# Vario_0_1_Ultra_Mini.net
KiCad netlist of a schematic drawn in EAGLE
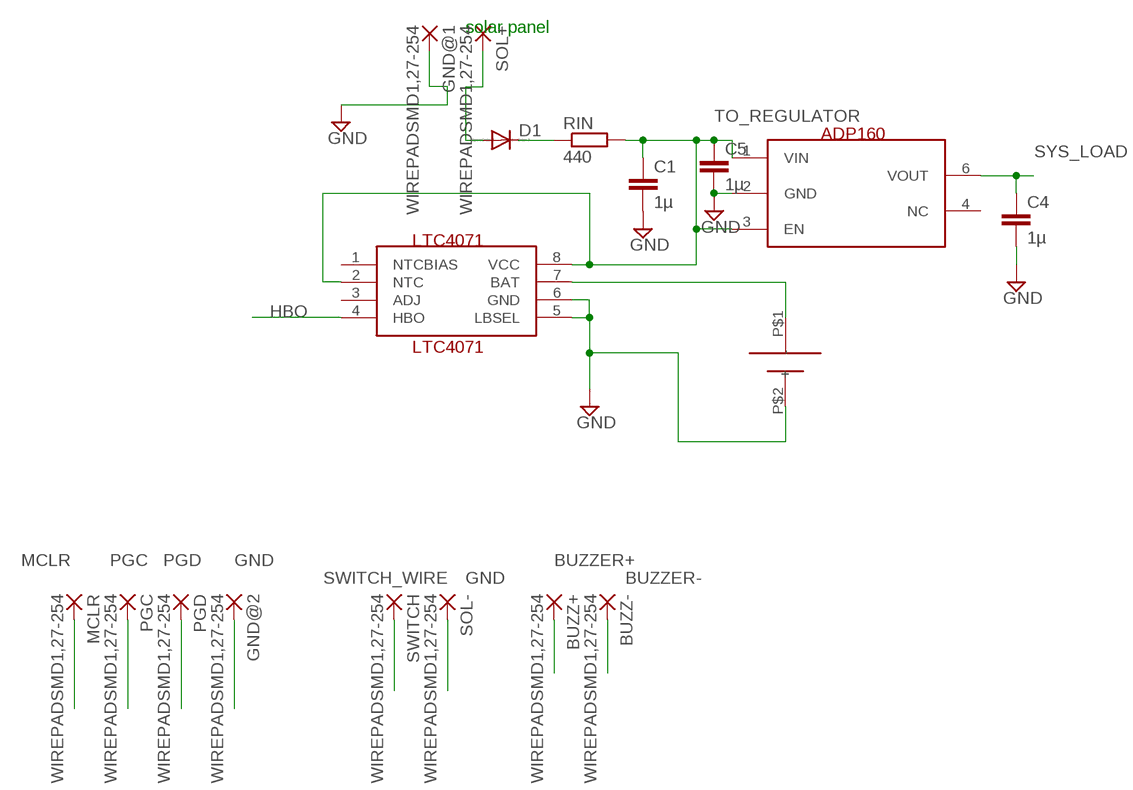
[diagram p0: schematic, sheet 1]
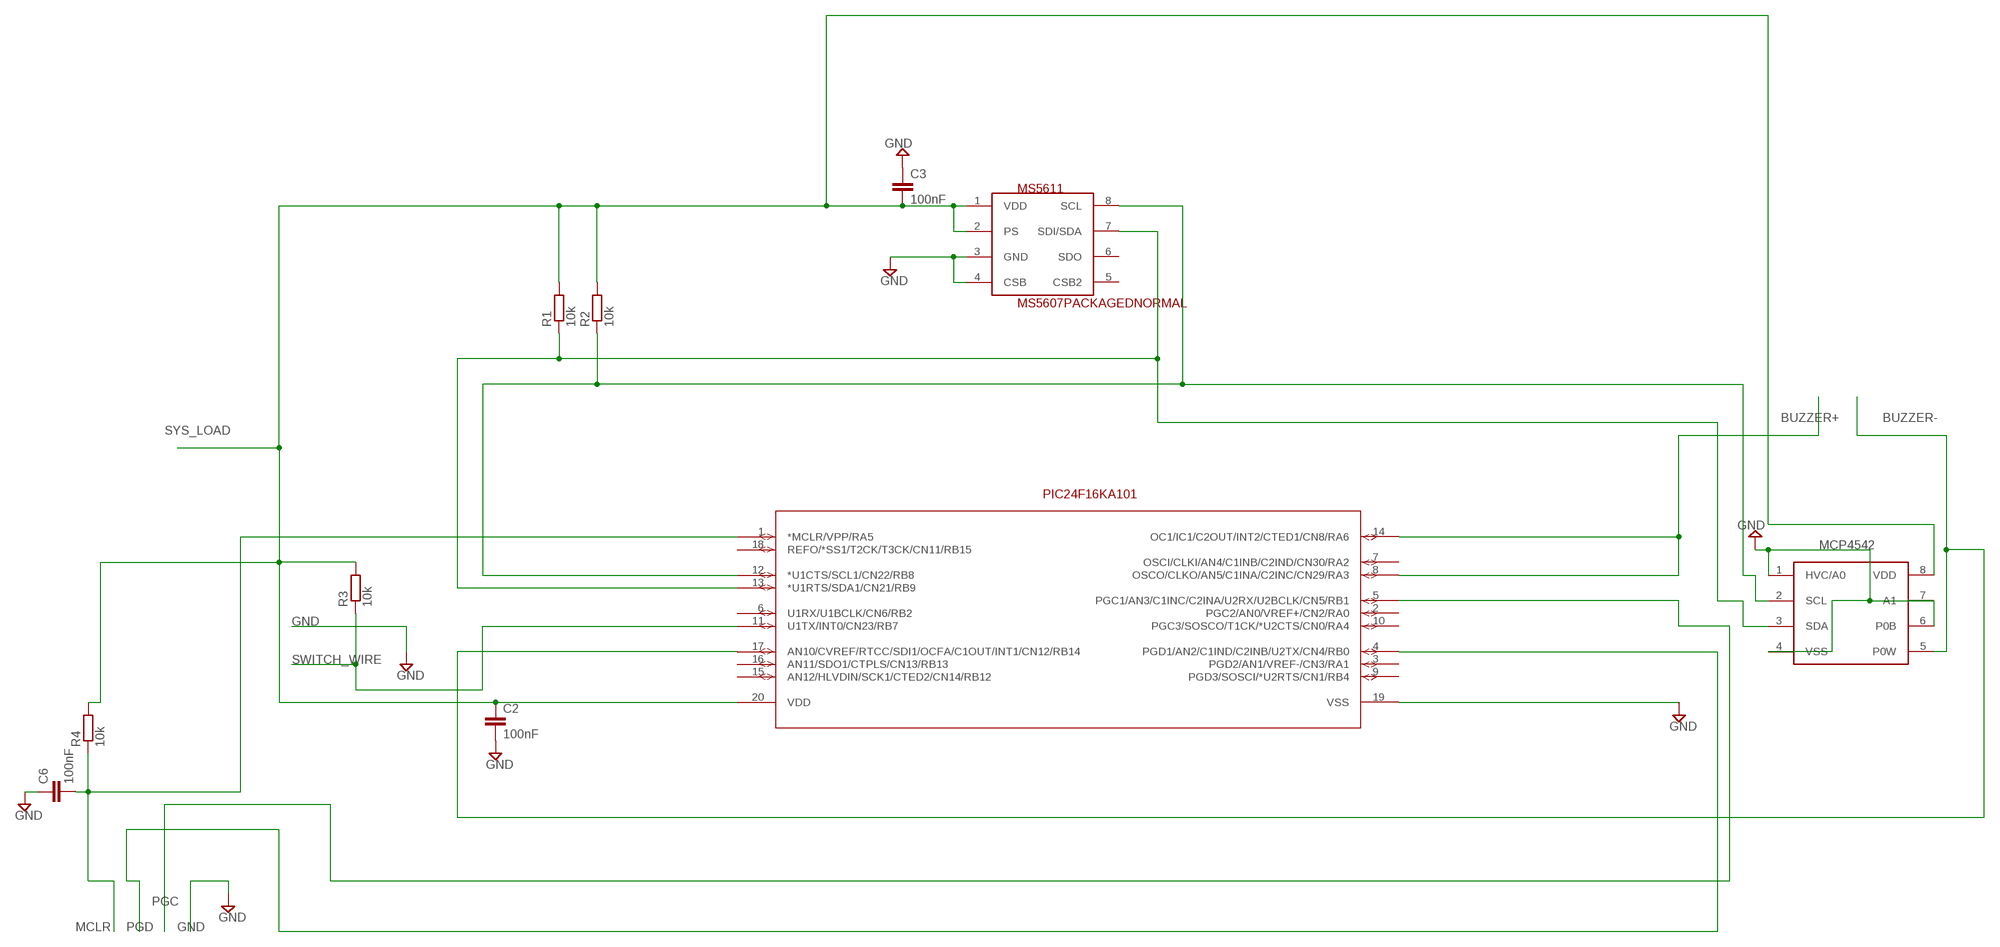
[diagram p1: schematic, sheet 2]

(export (version "E")
  (design (tool "Eeschema 10.0.6"))
  (components
    (comp (ref "ADP160")
      (value "ADP160/161/162/163")
      (footprint "eagle-import:TSOT23-6_DDC")
      (libsource (lib "eagle-import") (part "ADP160/161/162/163"))
    )
    (comp (ref "BATT+")
      (value "VARIO_LIPO")
      (footprint "eagle-import:VARIO_LIPO")
      (libsource (lib "eagle-import") (part "VARIO_LIPO"))
    )
    (comp (ref "BUZZ+")
      (value "WIREPADSMD1,27-254")
      (footprint "eagle-import:SMD1,27-2,54")
      (libsource (lib "eagle-import") (part "WIREPADSMD1,27-254"))
    )
    (comp (ref "BUZZ-")
      (value "WIREPADSMD1,27-254")
      (footprint "eagle-import:SMD1,27-2,54")
      (libsource (lib "eagle-import") (part "WIREPADSMD1,27-254"))
    )
    (comp (ref "C1")
      (value "1µ")
      (footprint "eagle-import:C0603")
      (libsource (lib "eagle-import") (part "C-EUC0603"))
    )
    (comp (ref "C4")
      (value "1µ")
      (footprint "eagle-import:C0603")
      (libsource (lib "eagle-import") (part "C-EUC0603"))
    )
    (comp (ref "C5")
      (value "1µ")
      (footprint "eagle-import:C0603")
      (libsource (lib "eagle-import") (part "C-EUC0603"))
    )
    (comp (ref "D1")
      (value "DIODE-SOD323-R")
      (footprint "eagle-import:SOD323-R")
      (libsource (lib "eagle-import") (part "DIODE-SOD323-R"))
    )
    (comp (ref "GND@1")
      (value "WIREPADSMD1,27-254")
      (footprint "eagle-import:SMD1,27-2,54")
      (libsource (lib "eagle-import") (part "WIREPADSMD1,27-254"))
    )
    (comp (ref "GND@2")
      (value "WIREPADSMD1,27-254")
      (footprint "eagle-import:SMD1,27-2,54")
      (libsource (lib "eagle-import") (part "WIREPADSMD1,27-254"))
    )
    (comp (ref "LTC4071")
      (value "LTC4071")
      (footprint "eagle-import:MSOP8")
      (libsource (lib "eagle-import") (part "LTC4071"))
    )
    (comp (ref "MCLR")
      (value "WIREPADSMD1,27-254")
      (footprint "eagle-import:SMD1,27-2,54")
      (libsource (lib "eagle-import") (part "WIREPADSMD1,27-254"))
    )
    (comp (ref "PGC")
      (value "WIREPADSMD1,27-254")
      (footprint "eagle-import:SMD1,27-2,54")
      (libsource (lib "eagle-import") (part "WIREPADSMD1,27-254"))
    )
    (comp (ref "PGD")
      (value "WIREPADSMD1,27-254")
      (footprint "eagle-import:SMD1,27-2,54")
      (libsource (lib "eagle-import") (part "WIREPADSMD1,27-254"))
    )
    (comp (ref "RIN")
      (value "440")
      (footprint "eagle-import:R0603")
      (libsource (lib "eagle-import") (part "R-EU_R0603"))
    )
    (comp (ref "SOL+")
      (value "WIREPADSMD1,27-254")
      (footprint "eagle-import:SMD1,27-2,54")
      (libsource (lib "eagle-import") (part "WIREPADSMD1,27-254"))
    )
    (comp (ref "SOL-")
      (value "WIREPADSMD1,27-254")
      (footprint "eagle-import:SMD1,27-2,54")
      (libsource (lib "eagle-import") (part "WIREPADSMD1,27-254"))
    )
    (comp (ref "SWITCH")
      (value "WIREPADSMD1,27-254")
      (footprint "eagle-import:SMD1,27-2,54")
      (libsource (lib "eagle-import") (part "WIREPADSMD1,27-254"))
    )
    (comp (ref "C2")
      (value "100nF")
      (footprint "eagle-import:C0603")
      (libsource (lib "eagle-import") (part "C-EUC0603"))
    )
    (comp (ref "C3")
      (value "100nF")
      (footprint "eagle-import:C0603")
      (libsource (lib "eagle-import") (part "C-EUC0603"))
    )
    (comp (ref "C6")
      (value "100nF")
      (footprint "eagle-import:C0603")
      (libsource (lib "eagle-import") (part "C-EUC0603"))
    )
    (comp (ref "MCP4542")
      (value "MCP4542")
      (footprint "eagle-import:MSOP8")
      (libsource (lib "eagle-import") (part "MCP4542"))
    )
    (comp (ref "MS5611")
      (value "MS5607PACKAGEDNORMAL")
      (footprint "eagle-import:MS5607-02BA03")
      (libsource (lib "eagle-import") (part "MS5607PACKAGEDNORMAL"))
    )
    (comp (ref "PIC24F16KA101")
      (value "PIC24F16KA101-X_")
      (footprint "eagle-import:SSOP20_MC")
      (libsource (lib "eagle-import") (part "PIC24F16KA101-X_"))
    )
    (comp (ref "R1")
      (value "10k")
      (footprint "eagle-import:R0603")
      (libsource (lib "eagle-import") (part "R-EU_R0603"))
    )
    (comp (ref "R2")
      (value "10k")
      (footprint "eagle-import:R0603")
      (libsource (lib "eagle-import") (part "R-EU_R0603"))
    )
    (comp (ref "R3")
      (value "10k")
      (footprint "eagle-import:R0603")
      (libsource (lib "eagle-import") (part "R-EU_R0603"))
    )
    (comp (ref "R4")
      (value "10k")
      (footprint "eagle-import:R0603")
      (libsource (lib "eagle-import") (part "R-EU_R0603"))
    )
  )
  (nets
    (net (code "1") (name "BUZZER+") (class "Default")
      (node (ref "BUZZ+") (pin "1") (pinfunction "P_1") (pintype "passive"))
      (node (ref "PIC24F16KA101") (pin "14") (pinfunction "OC1/IC1/C2OUT/INT2/CTED1/CN8/RA6_14") (pintype "passive"))
      (node (ref "PIC24F16KA101") (pin "8") (pinfunction "OSCO/CLKO/AN5/C1INA/C2INC/CN29/RA3_8") (pintype "passive"))
    )
    (net (code "2") (name "BUZZER-") (class "Default")
      (node (ref "BUZZ-") (pin "1") (pinfunction "P_1") (pintype "passive"))
      (node (ref "MCP4542") (pin "5") (pinfunction "P0W_5") (pintype "bidirectional"))
      (node (ref "PIC24F16KA101") (pin "17") (pinfunction "AN10/CVREF/RTCC/SDI1/OCFA/C1OUT/INT1/CN12/RB14_17") (pintype "passive"))
    )
    (net (code "3") (name "GND") (class "Default")
      (node (ref "ADP160") (pin "2") (pinfunction "GND_2") (pintype "power_in"))
      (node (ref "BATT+") (pin "P$2") (pinfunction "-_P$2") (pintype "bidirectional"))
      (node (ref "C1") (pin "2") (pinfunction "2_2") (pintype "passive"))
      (node (ref "C2") (pin "2") (pinfunction "2_2") (pintype "passive"))
      (node (ref "C3") (pin "1") (pinfunction "1_1") (pintype "passive"))
      (node (ref "C4") (pin "2") (pinfunction "2_2") (pintype "passive"))
      (node (ref "C5") (pin "2") (pinfunction "2_2") (pintype "passive"))
      (node (ref "C6") (pin "1") (pinfunction "1_1") (pintype "passive"))
      (node (ref "GND@1") (pin "1") (pinfunction "P_1") (pintype "passive"))
      (node (ref "GND@2") (pin "1") (pinfunction "P_1") (pintype "passive"))
      (node (ref "LTC4071") (pin "5") (pinfunction "LBSEL_5") (pintype "output"))
      (node (ref "LTC4071") (pin "6") (pinfunction "GND_6") (pintype "input"))
      (node (ref "MCP4542") (pin "1") (pinfunction "HVC/A0_1") (pintype "input"))
      (node (ref "MCP4542") (pin "4") (pinfunction "VSS_4") (pintype "bidirectional"))
      (node (ref "MCP4542") (pin "6") (pinfunction "P0B_6") (pintype "bidirectional"))
      (node (ref "MCP4542") (pin "7") (pinfunction "A1_7") (pintype "bidirectional"))
      (node (ref "MS5611") (pin "3") (pinfunction "GND_3") (pintype "power_in"))
      (node (ref "MS5611") (pin "4") (pinfunction "CSB_4") (pintype "input"))
      (node (ref "PIC24F16KA101") (pin "19") (pinfunction "VSS_19") (pintype "passive"))
      (node (ref "SOL-") (pin "1") (pinfunction "P_1") (pintype "passive"))
    )
    (net (code "4") (name "HBO") (class "Default")
      (node (ref "LTC4071") (pin "4") (pinfunction "HBO_4") (pintype "output"))
    )
    (net (code "5") (name "MCLR") (class "Default")
      (node (ref "C6") (pin "2") (pinfunction "2_2") (pintype "passive"))
      (node (ref "MCLR") (pin "1") (pinfunction "P_1") (pintype "passive"))
      (node (ref "PIC24F16KA101") (pin "1") (pinfunction "*MCLR/VPP/RA5_1") (pintype "passive"))
      (node (ref "R4") (pin "1") (pinfunction "1_1") (pintype "passive"))
    )
    (net (code "6") (name "Net-(BATT+-+)") (class "Default")
      (node (ref "BATT+") (pin "P$1") (pinfunction "+_P$1") (pintype "bidirectional"))
      (node (ref "LTC4071") (pin "7") (pinfunction "BAT_7") (pintype "bidirectional"))
    )
    (net (code "7") (name "Net-(D1-PadC)") (class "Default")
      (node (ref "D1") (pin "C") (pinfunction "C_C") (pintype "passive"))
      (node (ref "RIN") (pin "1") (pinfunction "1_1") (pintype "passive"))
    )
    (net (code "8") (name "Net-(MCP4542-SCL)") (class "Default")
      (node (ref "MCP4542") (pin "2") (pinfunction "SCL_2") (pintype "bidirectional"))
      (node (ref "MS5611") (pin "8") (pinfunction "SCL_8") (pintype "input"))
      (node (ref "PIC24F16KA101") (pin "12") (pinfunction "*U1CTS/SCL1/CN22/RB8_12") (pintype "passive"))
      (node (ref "R2") (pin "1") (pinfunction "1_1") (pintype "passive"))
    )
    (net (code "9") (name "Net-(MCP4542-SDA)") (class "Default")
      (node (ref "MCP4542") (pin "3") (pinfunction "SDA_3") (pintype "bidirectional"))
      (node (ref "MS5611") (pin "7") (pinfunction "SDI/SDA_7") (pintype "bidirectional"))
      (node (ref "PIC24F16KA101") (pin "13") (pinfunction "*U1RTS/SDA1/CN21/RB9_13") (pintype "passive"))
      (node (ref "R1") (pin "1") (pinfunction "1_1") (pintype "passive"))
    )
    (net (code "10") (name "Net-(SOL+-P)") (class "Default")
      (node (ref "D1") (pin "A") (pinfunction "A_A") (pintype "passive"))
      (node (ref "SOL+") (pin "1") (pinfunction "P_1") (pintype "passive"))
    )
    (net (code "11") (name "PGC") (class "Default")
      (node (ref "PGC") (pin "1") (pinfunction "P_1") (pintype "passive"))
      (node (ref "PIC24F16KA101") (pin "5") (pinfunction "PGC1/AN3/C1INC/C2INA/U2RX/U2BCLK/CN5/RB1_5") (pintype "passive"))
    )
    (net (code "12") (name "PGD") (class "Default")
      (node (ref "PGD") (pin "1") (pinfunction "P_1") (pintype "passive"))
      (node (ref "PIC24F16KA101") (pin "4") (pinfunction "PGD1/AN2/C1IND/C2INB/U2TX/CN4/RB0_4") (pintype "passive"))
    )
    (net (code "13") (name "SWITCH_WIRE") (class "Default")
      (node (ref "PIC24F16KA101") (pin "11") (pinfunction "U1TX/INT0/CN23/RB7_11") (pintype "passive"))
      (node (ref "R3") (pin "1") (pinfunction "1_1") (pintype "passive"))
      (node (ref "SWITCH") (pin "1") (pinfunction "P_1") (pintype "passive"))
    )
    (net (code "14") (name "SYS_LOAD") (class "Default")
      (node (ref "ADP160") (pin "6") (pinfunction "VOUT_6") (pintype "bidirectional"))
      (node (ref "C2") (pin "1") (pinfunction "1_1") (pintype "passive"))
      (node (ref "C3") (pin "2") (pinfunction "2_2") (pintype "passive"))
      (node (ref "C4") (pin "1") (pinfunction "1_1") (pintype "passive"))
      (node (ref "MCP4542") (pin "8") (pinfunction "VDD_8") (pintype "bidirectional"))
      (node (ref "MS5611") (pin "1") (pinfunction "VDD_1") (pintype "power_in"))
      (node (ref "MS5611") (pin "2") (pinfunction "PS_2") (pintype "input"))
      (node (ref "PIC24F16KA101") (pin "20") (pinfunction "VDD_20") (pintype "passive"))
      (node (ref "R1") (pin "2") (pinfunction "2_2") (pintype "passive"))
      (node (ref "R2") (pin "2") (pinfunction "2_2") (pintype "passive"))
      (node (ref "R3") (pin "2") (pinfunction "2_2") (pintype "passive"))
      (node (ref "R4") (pin "2") (pinfunction "2_2") (pintype "passive"))
    )
    (net (code "15") (name "TO_REGULATOR") (class "Default")
      (node (ref "ADP160") (pin "1") (pinfunction "VIN_1") (pintype "tri_state"))
      (node (ref "ADP160") (pin "3") (pinfunction "EN_3") (pintype "input"))
      (node (ref "C1") (pin "1") (pinfunction "1_1") (pintype "passive"))
      (node (ref "C5") (pin "1") (pinfunction "1_1") (pintype "passive"))
      (node (ref "LTC4071") (pin "2") (pinfunction "NTC_2") (pintype "input"))
      (node (ref "LTC4071") (pin "8") (pinfunction "VCC_8") (pintype "input"))
      (node (ref "RIN") (pin "2") (pinfunction "2_2") (pintype "passive"))
    )
    (net (code "16") (name "unconnected-(ADP160-NC-Pad4)") (class "Default")
      (node (ref "ADP160") (pin "4") (pinfunction "NC_4") (pintype "no_connect"))
    )
    (net (code "17") (name "unconnected-(LTC4071-ADJ-Pad3)") (class "Default")
      (node (ref "LTC4071") (pin "3") (pinfunction "ADJ_3") (pintype "output"))
    )
    (net (code "18") (name "unconnected-(LTC4071-NTCBIAS-Pad1)") (class "Default")
      (node (ref "LTC4071") (pin "1") (pinfunction "NTCBIAS_1") (pintype "input"))
    )
    (net (code "19") (name "unconnected-(MS5611-CSB2-Pad5)") (class "Default")
      (node (ref "MS5611") (pin "5") (pinfunction "CSB2_5") (pintype "input"))
    )
    (net (code "20") (name "unconnected-(MS5611-SDO-Pad6)") (class "Default")
      (node (ref "MS5611") (pin "6") (pinfunction "SDO_6") (pintype "output"))
    )
    (net (code "21") (name "unconnected-(PIC24F16KA101-AN11{slash}SDO1{slash}CTPLS{slash}CN13{slash}RB13-Pad16)") (class "Default")
      (node (ref "PIC24F16KA101") (pin "16") (pinfunction "AN11/SDO1/CTPLS/CN13/RB13_16") (pintype "passive"))
    )
    (net (code "22") (name "unconnected-(PIC24F16KA101-AN12{slash}HLVDIN{slash}SCK1{slash}CTED2{slash}CN14{slash}RB12-Pad15)") (class "Default")
      (node (ref "PIC24F16KA101") (pin "15") (pinfunction "AN12/HLVDIN/SCK1/CTED2/CN14/RB12_15") (pintype "passive"))
    )
    (net (code "23") (name "unconnected-(PIC24F16KA101-OSCI{slash}CLKI{slash}AN4{slash}C1INB{slash}C2IND{slash}CN30{slash}RA2-Pad7)") (class "Default")
      (node (ref "PIC24F16KA101") (pin "7") (pinfunction "OSCI/CLKI/AN4/C1INB/C2IND/CN30/RA2_7") (pintype "passive"))
    )
    (net (code "24") (name "unconnected-(PIC24F16KA101-PGC2{slash}AN0{slash}VREF+{slash}CN2{slash}RA0-Pad2)") (class "Default")
      (node (ref "PIC24F16KA101") (pin "2") (pinfunction "PGC2/AN0/VREF+/CN2/RA0_2") (pintype "passive"))
    )
    (net (code "25") (name "unconnected-(PIC24F16KA101-PGC3{slash}SOSCO{slash}T1CK{slash}*U2CTS{slash}CN0{slash}RA4-Pad10)") (class "Default")
      (node (ref "PIC24F16KA101") (pin "10") (pinfunction "PGC3/SOSCO/T1CK/*U2CTS/CN0/RA4_10") (pintype "passive"))
    )
    (net (code "26") (name "unconnected-(PIC24F16KA101-PGD2{slash}AN1{slash}VREF-{slash}CN3{slash}RA1-Pad3)") (class "Default")
      (node (ref "PIC24F16KA101") (pin "3") (pinfunction "PGD2/AN1/VREF-/CN3/RA1_3") (pintype "passive"))
    )
    (net (code "27") (name "unconnected-(PIC24F16KA101-PGD3{slash}SOSCI{slash}*U2RTS{slash}CN1{slash}RB4-Pad9)") (class "Default")
      (node (ref "PIC24F16KA101") (pin "9") (pinfunction "PGD3/SOSCI/*U2RTS/CN1/RB4_9") (pintype "passive"))
    )
    (net (code "28") (name "unconnected-(PIC24F16KA101-REFO{slash}*SS1{slash}T2CK{slash}T3CK{slash}CN11{slash}RB15-Pad18)") (class "Default")
      (node (ref "PIC24F16KA101") (pin "18") (pinfunction "REFO/*SS1/T2CK/T3CK/CN11/RB15_18") (pintype "passive"))
    )
    (net (code "29") (name "unconnected-(PIC24F16KA101-U1RX{slash}U1BCLK{slash}CN6{slash}RB2-Pad6)") (class "Default")
      (node (ref "PIC24F16KA101") (pin "6") (pinfunction "U1RX/U1BCLK/CN6/RB2_6") (pintype "passive"))
    )
  )
)
